# target.net
KiCad netlist of a schematic drawn in EAGLE
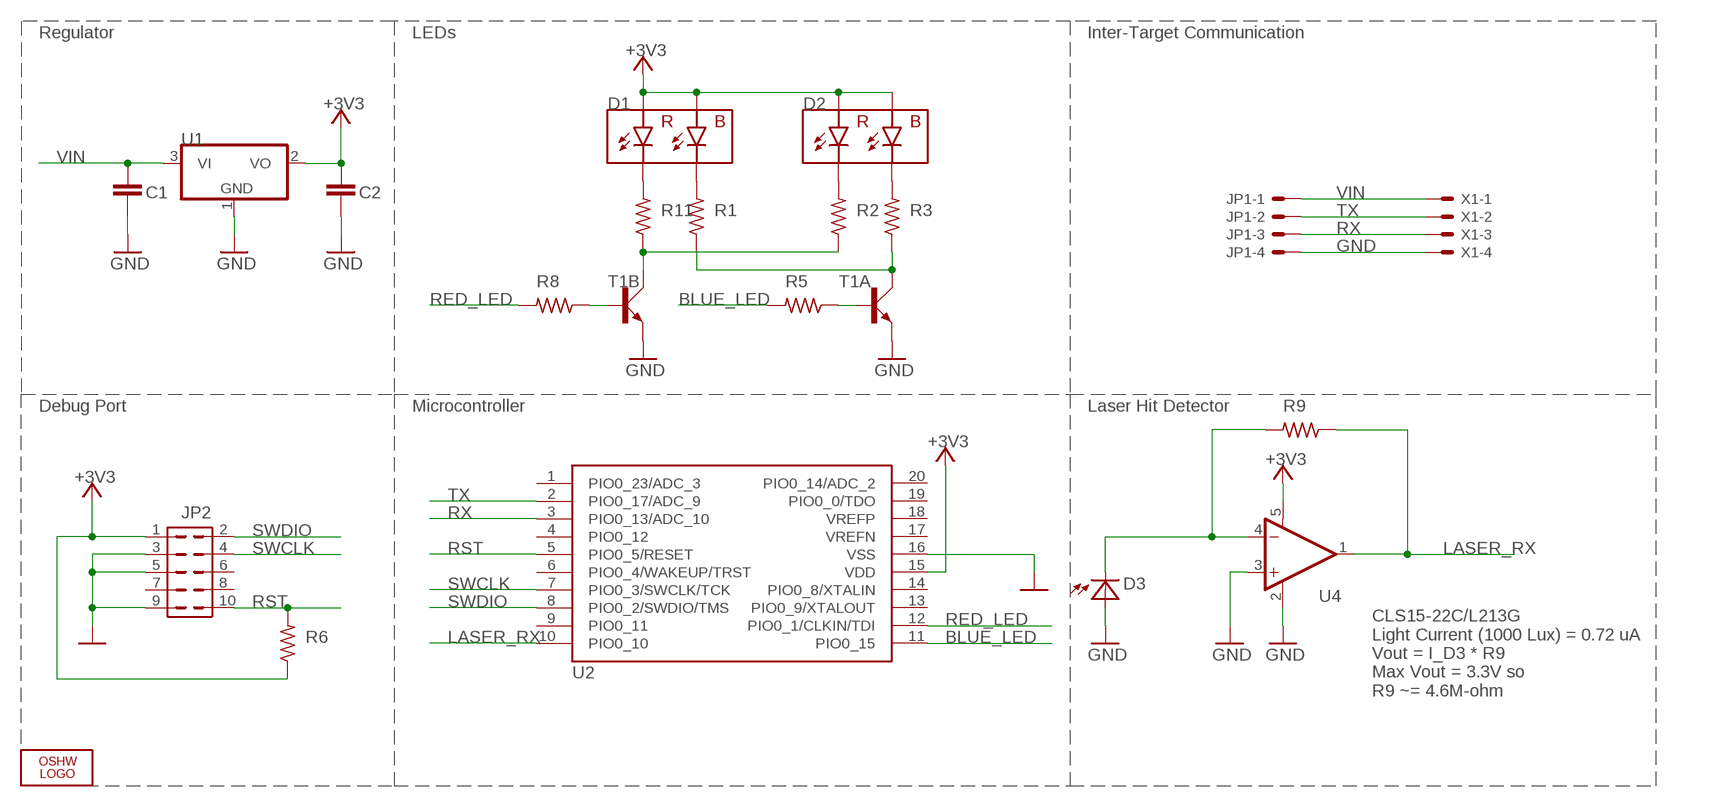
[diagram p0: schematic, sheet 1]

(export (version "E")
  (design (tool "Eeschema 10.0.6"))
  (components
    (comp (ref "C1")
      (value "C1608X5R1C106M080AB")
      (footprint "eagle-import:0603-CAP")
      (libsource (lib "eagle-import") (part "CAP0603-CAP"))
    )
    (comp (ref "C2")
      (value "C1608X5R1C106M080AB")
      (footprint "eagle-import:0603-CAP")
      (libsource (lib "eagle-import") (part "CAP0603-CAP"))
    )
    (comp (ref "D1")
      (value "150141RB73100")
      (footprint "eagle-import:150141RB")
      (libsource (lib "eagle-import") (part "LED_RB"))
    )
    (comp (ref "D2")
      (value "150141RB73100")
      (footprint "eagle-import:150141RB")
      (libsource (lib "eagle-import") (part "LED_RB"))
    )
    (comp (ref "D3")
      (value "638-CLS1522CL213GTR8")
      (footprint "eagle-import:CLS15")
      (libsource (lib "eagle-import") (part "CLS15CLS15"))
    )
    (comp (ref "JP1")
      (value "798-DF134P125V20")
      (footprint "eagle-import:53398-04")
      (libsource (lib "eagle-import") (part "53?-04398"))
    )
    (comp (ref "JP2")
      (value "FTSH-105-01-L")
      (footprint "eagle-import:FTSH-105-01-XXX-DV-K")
      (libsource (lib "eagle-import") (part "FTSH-105"))
    )
    (comp (ref "LOGO2")
      (value "OSHW_LOGO_FILLX0150-NT")
      (footprint "eagle-import:OSHW_FILLX150_NOTEXT")
      (libsource (lib "eagle-import") (part "OSHW_LOGO_FILLX0150-NT"))
    )
    (comp (ref "R1")
      (value "71-CRCW0603-5.6-E3")
      (footprint "eagle-import:R0603")
      (libsource (lib "eagle-import") (part "R-US_R0603"))
    )
    (comp (ref "R2")
      (value "71-CRCW060368R0FKEB")
      (footprint "eagle-import:R0603")
      (libsource (lib "eagle-import") (part "R-US_R0603"))
    )
    (comp (ref "R3")
      (value "71-CRCW0603-5.6-E3")
      (footprint "eagle-import:R0603")
      (libsource (lib "eagle-import") (part "R-US_R0603"))
    )
    (comp (ref "R5")
      (value "71-CRCW0603220RFKEB")
      (footprint "eagle-import:R0603")
      (libsource (lib "eagle-import") (part "R-US_R0603"))
    )
    (comp (ref "R6")
      (value "71-CRCW0603-10K-E3")
      (footprint "eagle-import:R0603")
      (libsource (lib "eagle-import") (part "R-US_R0603"))
    )
    (comp (ref "R8")
      (value "71-CRCW0603220RFKEB")
      (footprint "eagle-import:R0603")
      (libsource (lib "eagle-import") (part "R-US_R0603"))
    )
    (comp (ref "R9")
      (value "71-CRCW06034M64FKEA")
      (footprint "eagle-import:R0603")
      (libsource (lib "eagle-import") (part "R-US_R0603"))
    )
    (comp (ref "R11")
      (value "71-CRCW060368R0FKEB")
      (footprint "eagle-import:R0603")
      (libsource (lib "eagle-import") (part "R-US_R0603"))
    )
    (comp (ref "T1")
      (value "771-BC847BS-T/R")
      (footprint "eagle-import:SOT363_PHILIPS")
      (libsource (lib "eagle-import") (part "BC847BS"))
    )
    (comp (ref "U1")
      (value "579-MCP1703T-3002ECB")
      (footprint "eagle-import:SOT23")
      (libsource (lib "eagle-import") (part "MCP1703CB"))
    )
    (comp (ref "U2")
      (value "771-LPC824M201JDH20J")
      (footprint "eagle-import:TSSOP20")
      (libsource (lib "eagle-import") (part "LPC824"))
    )
    (comp (ref "U4")
      (value "579-MCP6291T-E/OT")
      (footprint "eagle-import:SOT23-5")
      (libsource (lib "eagle-import") (part "MCP6291T-E/OT"))
    )
    (comp (ref "X1")
      (value "798-DF134P125V20")
      (footprint "eagle-import:53398-04")
      (libsource (lib "eagle-import") (part "53?-04398"))
    )
  )
  (nets
    (net (code "1") (name "+3V3") (class "Default")
      (node (ref "C2") (pin "1") (pinfunction "1_1") (pintype "passive"))
      (node (ref "D1") (pin "1") (pinfunction "1_1") (pintype "passive"))
      (node (ref "D1") (pin "2") (pinfunction "2_2") (pintype "passive"))
      (node (ref "D2") (pin "1") (pinfunction "1_1") (pintype "passive"))
      (node (ref "D2") (pin "2") (pinfunction "2_2") (pintype "passive"))
      (node (ref "JP2") (pin "1") (pinfunction "1_1") (pintype "passive"))
      (node (ref "R6") (pin "1") (pinfunction "1_1") (pintype "passive"))
      (node (ref "U1") (pin "2") (pinfunction "VO_2") (pintype "passive"))
      (node (ref "U2") (pin "15") (pinfunction "VDD_15") (pintype "bidirectional"))
      (node (ref "U4") (pin "5") (pinfunction "V+_5") (pintype "power_in"))
    )
    (net (code "2") (name "/BLUE_LED") (class "Default")
      (node (ref "R5") (pin "2") (pinfunction "2_2") (pintype "passive"))
      (node (ref "U2") (pin "11") (pinfunction "PIO0_15_11") (pintype "bidirectional"))
    )
    (net (code "3") (name "/LASER_RX") (class "Default")
      (node (ref "R9") (pin "1") (pinfunction "1_1") (pintype "passive"))
      (node (ref "U2") (pin "10") (pinfunction "PIO0_10_10") (pintype "bidirectional"))
      (node (ref "U4") (pin "1") (pinfunction "OUT_1") (pintype "output"))
    )
    (net (code "4") (name "/RED_LED") (class "Default")
      (node (ref "R8") (pin "2") (pinfunction "2_2") (pintype "passive"))
      (node (ref "U2") (pin "12") (pinfunction "PIO0_1/CLKIN/TDI_12") (pintype "bidirectional"))
    )
    (net (code "5") (name "/RST") (class "Default")
      (node (ref "JP2") (pin "10") (pinfunction "10_10") (pintype "passive"))
      (node (ref "R6") (pin "2") (pinfunction "2_2") (pintype "passive"))
      (node (ref "U2") (pin "5") (pinfunction "PIO0_5/RESET_5") (pintype "bidirectional"))
    )
    (net (code "6") (name "/RX") (class "Default")
      (node (ref "JP1") (pin "3") (pinfunction "S_3") (pintype "passive"))
      (node (ref "U2") (pin "3") (pinfunction "PIO0_13/ADC_10_3") (pintype "bidirectional"))
      (node (ref "X1") (pin "3") (pinfunction "S_3") (pintype "passive"))
    )
    (net (code "7") (name "/SWCLK") (class "Default")
      (node (ref "JP2") (pin "4") (pinfunction "4_4") (pintype "passive"))
      (node (ref "U2") (pin "7") (pinfunction "PIO0_3/SWCLK/TCK_7") (pintype "bidirectional"))
    )
    (net (code "8") (name "/SWDIO") (class "Default")
      (node (ref "JP2") (pin "2") (pinfunction "2_2") (pintype "passive"))
      (node (ref "U2") (pin "8") (pinfunction "PIO0_2/SWDIO/TMS_8") (pintype "bidirectional"))
    )
    (net (code "9") (name "/TX") (class "Default")
      (node (ref "JP1") (pin "2") (pinfunction "S_2") (pintype "passive"))
      (node (ref "U2") (pin "2") (pinfunction "PIO0_17/ADC_9_2") (pintype "bidirectional"))
      (node (ref "X1") (pin "2") (pinfunction "S_2") (pintype "passive"))
    )
    (net (code "10") (name "/VIN") (class "Default")
      (node (ref "C1") (pin "1") (pinfunction "1_1") (pintype "passive"))
      (node (ref "JP1") (pin "1") (pinfunction "S_1") (pintype "passive"))
      (node (ref "U1") (pin "3") (pinfunction "VI_3") (pintype "input"))
      (node (ref "X1") (pin "1") (pinfunction "S_1") (pintype "passive"))
    )
    (net (code "11") (name "GND") (class "Default")
      (node (ref "C1") (pin "2") (pinfunction "2_2") (pintype "passive"))
      (node (ref "C2") (pin "2") (pinfunction "2_2") (pintype "passive"))
      (node (ref "D3") (pin "1") (pinfunction "A_1") (pintype "passive"))
      (node (ref "D3") (pin "2") (pinfunction "A_2") (pintype "passive"))
      (node (ref "JP1") (pin "4") (pinfunction "S_4") (pintype "passive"))
      (node (ref "JP2") (pin "3") (pinfunction "3_3") (pintype "passive"))
      (node (ref "JP2") (pin "5") (pinfunction "5_5") (pintype "passive"))
      (node (ref "JP2") (pin "9") (pinfunction "9_9") (pintype "passive"))
      (node (ref "T1") (pin "1") (pinfunction "E_1") (pintype "passive"))
      (node (ref "T1") (pin "4") (pinfunction "E_4") (pintype "passive"))
      (node (ref "U1") (pin "1") (pinfunction "GND_1") (pintype "passive"))
      (node (ref "U2") (pin "16") (pinfunction "VSS_16") (pintype "bidirectional"))
      (node (ref "U4") (pin "2") (pinfunction "V-_2") (pintype "power_in"))
      (node (ref "U4") (pin "3") (pinfunction "+IN_3") (pintype "input"))
      (node (ref "X1") (pin "4") (pinfunction "S_4") (pintype "passive"))
    )
    (net (code "12") (name "Net-(D1-Pad3)") (class "Default")
      (node (ref "D1") (pin "3") (pinfunction "3_3") (pintype "passive"))
      (node (ref "R11") (pin "2") (pinfunction "2_2") (pintype "passive"))
    )
    (net (code "13") (name "Net-(D1-Pad4)") (class "Default")
      (node (ref "D1") (pin "4") (pinfunction "4_4") (pintype "passive"))
      (node (ref "R1") (pin "2") (pinfunction "2_2") (pintype "passive"))
    )
    (net (code "14") (name "Net-(D2-Pad3)") (class "Default")
      (node (ref "D2") (pin "3") (pinfunction "3_3") (pintype "passive"))
      (node (ref "R2") (pin "2") (pinfunction "2_2") (pintype "passive"))
    )
    (net (code "15") (name "Net-(D2-Pad4)") (class "Default")
      (node (ref "D2") (pin "4") (pinfunction "4_4") (pintype "passive"))
      (node (ref "R3") (pin "2") (pinfunction "2_2") (pintype "passive"))
    )
    (net (code "16") (name "Net-(T1A-B)") (class "Default")
      (node (ref "R5") (pin "1") (pinfunction "1_1") (pintype "passive"))
      (node (ref "T1") (pin "2") (pinfunction "B_2") (pintype "passive"))
    )
    (net (code "17") (name "Net-(T1A-C)") (class "Default")
      (node (ref "R1") (pin "1") (pinfunction "1_1") (pintype "passive"))
      (node (ref "R3") (pin "1") (pinfunction "1_1") (pintype "passive"))
      (node (ref "T1") (pin "6") (pinfunction "C_6") (pintype "passive"))
    )
    (net (code "18") (name "Net-(T1B-B)") (class "Default")
      (node (ref "R8") (pin "1") (pinfunction "1_1") (pintype "passive"))
      (node (ref "T1") (pin "5") (pinfunction "B_5") (pintype "passive"))
    )
    (net (code "19") (name "Net-(T1B-C)") (class "Default")
      (node (ref "R11") (pin "1") (pinfunction "1_1") (pintype "passive"))
      (node (ref "R2") (pin "1") (pinfunction "1_1") (pintype "passive"))
      (node (ref "T1") (pin "3") (pinfunction "C_3") (pintype "passive"))
    )
    (net (code "20") (name "Net-(U4--IN)") (class "Default")
      (node (ref "D3") (pin "3") (pinfunction "C_3") (pintype "passive"))
      (node (ref "D3") (pin "4") (pinfunction "C_4") (pintype "passive"))
      (node (ref "R9") (pin "2") (pinfunction "2_2") (pintype "passive"))
      (node (ref "U4") (pin "4") (pinfunction "-IN_4") (pintype "input"))
    )
    (net (code "21") (name "unconnected-(JP2-Pad6)") (class "Default")
      (node (ref "JP2") (pin "6") (pinfunction "6_6") (pintype "passive"))
    )
    (net (code "22") (name "unconnected-(JP2-Pad7)") (class "Default")
      (node (ref "JP2") (pin "7") (pinfunction "7_7") (pintype "passive"))
    )
    (net (code "23") (name "unconnected-(JP2-Pad8)") (class "Default")
      (node (ref "JP2") (pin "8") (pinfunction "8_8") (pintype "passive"))
    )
    (net (code "24") (name "unconnected-(U2-PIO0_0{slash}TDO-Pad19)") (class "Default")
      (node (ref "U2") (pin "19") (pinfunction "PIO0_0/TDO_19") (pintype "bidirectional"))
    )
    (net (code "25") (name "unconnected-(U2-PIO0_4{slash}WAKEUP{slash}TRST-Pad6)") (class "Default")
      (node (ref "U2") (pin "6") (pinfunction "PIO0_4/WAKEUP/TRST_6") (pintype "bidirectional"))
    )
    (net (code "26") (name "unconnected-(U2-PIO0_8{slash}XTALIN-Pad14)") (class "Default")
      (node (ref "U2") (pin "14") (pinfunction "PIO0_8/XTALIN_14") (pintype "bidirectional"))
    )
    (net (code "27") (name "unconnected-(U2-PIO0_9{slash}XTALOUT-Pad13)") (class "Default")
      (node (ref "U2") (pin "13") (pinfunction "PIO0_9/XTALOUT_13") (pintype "bidirectional"))
    )
    (net (code "28") (name "unconnected-(U2-PIO0_11-Pad9)") (class "Default")
      (node (ref "U2") (pin "9") (pinfunction "PIO0_11_9") (pintype "bidirectional"))
    )
    (net (code "29") (name "unconnected-(U2-PIO0_12-Pad4)") (class "Default")
      (node (ref "U2") (pin "4") (pinfunction "PIO0_12_4") (pintype "bidirectional"))
    )
    (net (code "30") (name "unconnected-(U2-PIO0_14{slash}ADC_2-Pad20)") (class "Default")
      (node (ref "U2") (pin "20") (pinfunction "PIO0_14/ADC_2_20") (pintype "bidirectional"))
    )
    (net (code "31") (name "unconnected-(U2-PIO0_23{slash}ADC_3-Pad1)") (class "Default")
      (node (ref "U2") (pin "1") (pinfunction "PIO0_23/ADC_3_1") (pintype "bidirectional"))
    )
    (net (code "32") (name "unconnected-(U2-VREFN-Pad17)") (class "Default")
      (node (ref "U2") (pin "17") (pinfunction "VREFN_17") (pintype "bidirectional"))
    )
    (net (code "33") (name "unconnected-(U2-VREFP-Pad18)") (class "Default")
      (node (ref "U2") (pin "18") (pinfunction "VREFP_18") (pintype "bidirectional"))
    )
  )
)
